# nanino.net
KiCad netlist of a schematic drawn in EAGLE
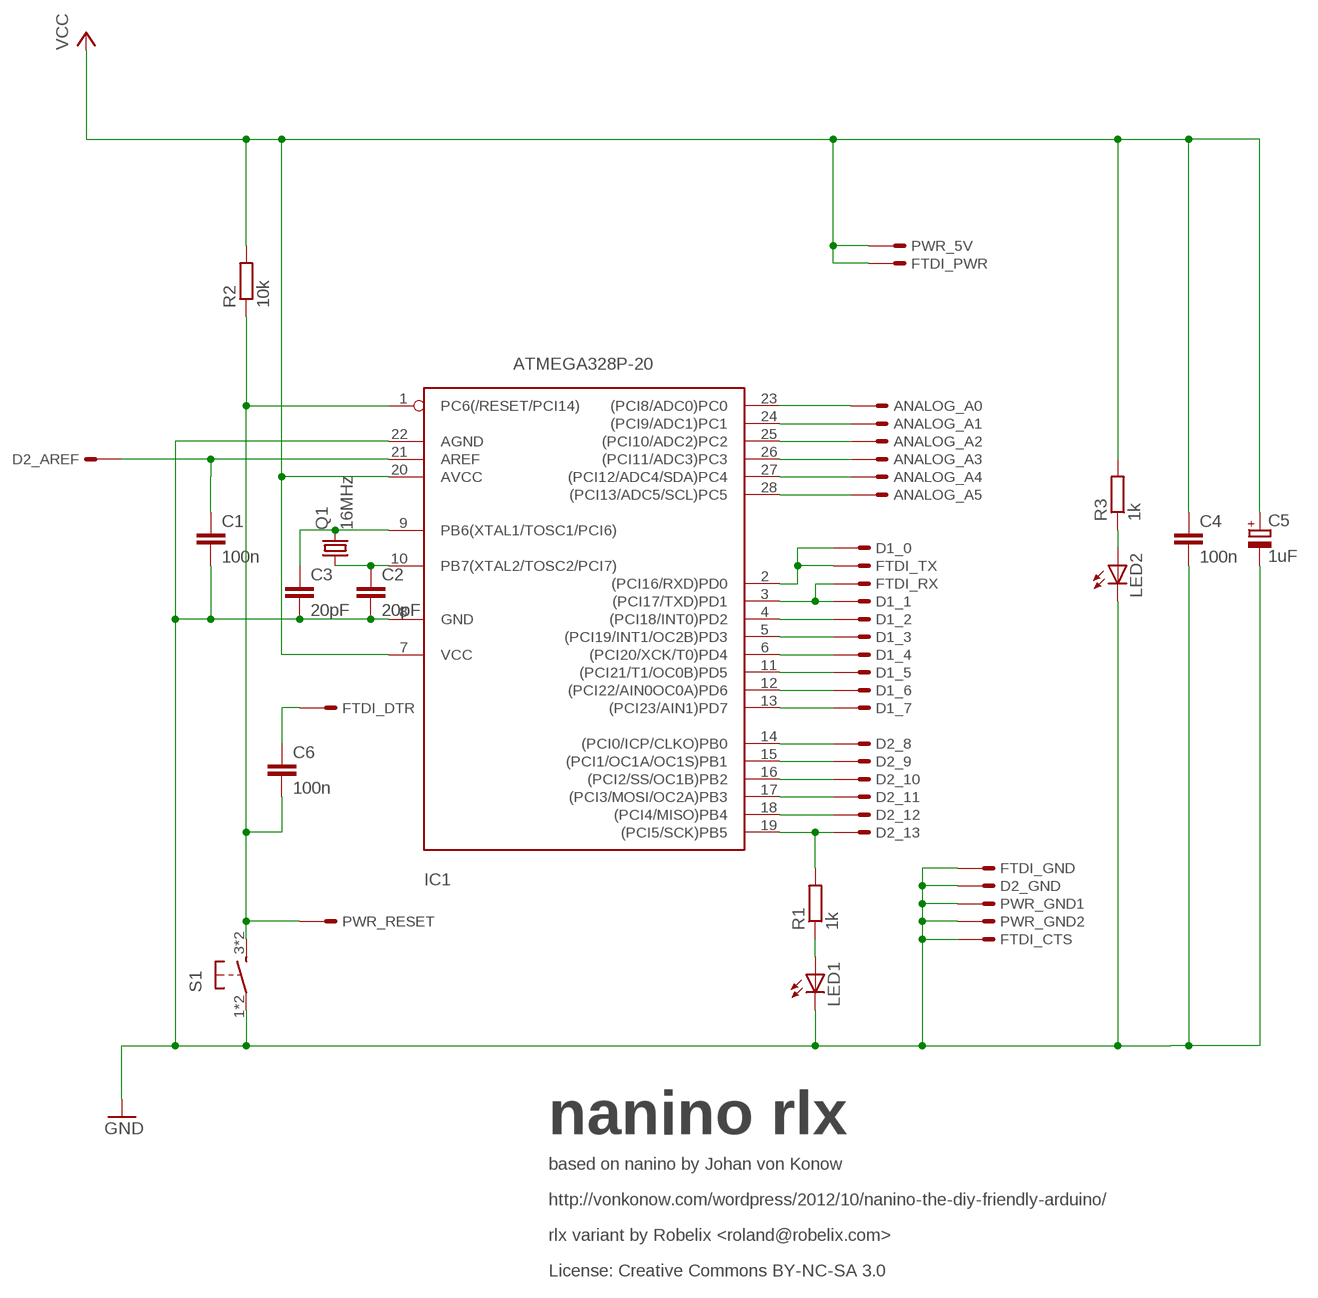
[diagram p0: schematic, sheet 1]

(export (version "E")
  (design (tool "Eeschema 10.0.6"))
  (components
    (comp (ref "ANALOG_")
      (value "PINS_ARDUINO_ANALOG1")
      (footprint "eagle-import:6PIN")
      (libsource (lib "eagle-import") (part "PINS_ARDUINO_ANALOG1"))
    )
    (comp (ref "C1")
      (value "100n")
      (footprint "eagle-import:C025-025X050")
      (libsource (lib "eagle-import") (part "C-EU025-025X050"))
    )
    (comp (ref "C2")
      (value "20pF")
      (footprint "eagle-import:C025-025X050")
      (libsource (lib "eagle-import") (part "C-EU025-025X050"))
    )
    (comp (ref "C3")
      (value "20pF")
      (footprint "eagle-import:C025-025X050")
      (libsource (lib "eagle-import") (part "C-EU025-025X050"))
    )
    (comp (ref "C4")
      (value "100n")
      (footprint "eagle-import:C025-025X050")
      (libsource (lib "eagle-import") (part "C-EU025-025X050"))
    )
    (comp (ref "C5")
      (value "1uF")
      (footprint "eagle-import:E2,5-5-L-12")
      (libsource (lib "eagle-import") (part "CPOL-EUE2.5-5-L-12"))
    )
    (comp (ref "C6")
      (value "100n")
      (footprint "eagle-import:C050-025X075")
      (libsource (lib "eagle-import") (part "C-EU050-025X075"))
    )
    (comp (ref "D1_")
      (value "PINS_ARDUINO_DIGITAL1")
      (footprint "eagle-import:8PIN")
      (libsource (lib "eagle-import") (part "PINS_ARDUINO_DIGITAL1"))
    )
    (comp (ref "D2_")
      (value "PINS_ARDUINO_DIGITAL2")
      (footprint "eagle-import:8PIN")
      (libsource (lib "eagle-import") (part "PINS_ARDUINO_DIGITAL2"))
    )
    (comp (ref "FTDI_")
      (value "PINS_FTDI1")
      (footprint "eagle-import:6PIN")
      (libsource (lib "eagle-import") (part "PINS_FTDI1"))
    )
    (comp (ref "IC1")
      (value "ATMEGA328P-20")
      (footprint "eagle-import:DIL28-3")
      (libsource (lib "eagle-import") (part "ATMEGA328P-20"))
    )
    (comp (ref "LED1")
      (value "LED3MM")
      (footprint "eagle-import:LED3MM")
      (libsource (lib "eagle-import") (part "LED3MM"))
    )
    (comp (ref "LED2")
      (value "LED3MM")
      (footprint "eagle-import:LED3MM")
      (libsource (lib "eagle-import") (part "LED3MM"))
    )
    (comp (ref "PWR_")
      (value "PINS_ARDUINO_PWR1")
      (footprint "eagle-import:6PIN")
      (libsource (lib "eagle-import") (part "PINS_ARDUINO_PWR1"))
    )
    (comp (ref "Q1")
      (value "16MHz")
      (footprint "eagle-import:HC49U-V")
      (libsource (lib "eagle-import") (part "CRYSTALHC49U-V"))
    )
    (comp (ref "R1")
      (value "1k")
      (footprint "eagle-import:0207_10")
      (libsource (lib "eagle-import") (part "R-EU_0207/10"))
    )
    (comp (ref "R2")
      (value "10k")
      (footprint "eagle-import:0207_10")
      (libsource (lib "eagle-import") (part "R-EU_0207/10"))
    )
    (comp (ref "R3")
      (value "1k")
      (footprint "eagle-import:0207_10")
      (libsource (lib "eagle-import") (part "R-EU_0207/10"))
    )
    (comp (ref "S1")
      (value "TASTER4.3MM")
      (footprint "eagle-import:TASTER6X6")
      (libsource (lib "eagle-import") (part "TASTER4.3MM"))
    )
  )
  (nets
    (net (code "1") (name "GND") (class "Default")
      (node (ref "C1") (pin "2") (pinfunction "2_2") (pintype "passive"))
      (node (ref "C2") (pin "2") (pinfunction "2_2") (pintype "passive"))
      (node (ref "C3") (pin "2") (pinfunction "2_2") (pintype "passive"))
      (node (ref "C4") (pin "2") (pinfunction "2_2") (pintype "passive"))
      (node (ref "C5") (pin "-") (pinfunction "-_-") (pintype "passive"))
      (node (ref "D2_") (pin "7") (pinfunction "S_7") (pintype "passive"))
      (node (ref "FTDI_") (pin "1") (pinfunction "S_1") (pintype "passive"))
      (node (ref "FTDI_") (pin "2") (pinfunction "S_2") (pintype "passive"))
      (node (ref "IC1") (pin "22") (pinfunction "AGND_22") (pintype "bidirectional"))
      (node (ref "IC1") (pin "8") (pinfunction "GND_8") (pintype "bidirectional"))
      (node (ref "LED1") (pin "K") (pinfunction "C_K") (pintype "passive"))
      (node (ref "LED2") (pin "K") (pinfunction "C_K") (pintype "passive"))
      (node (ref "PWR_") (pin "4") (pinfunction "S_4") (pintype "passive"))
      (node (ref "PWR_") (pin "5") (pinfunction "S_5") (pintype "passive"))
      (node (ref "S1") (pin "1") (pinfunction "1_1") (pintype "passive"))
      (node (ref "S1") (pin "2") (pinfunction "1_2") (pintype "passive"))
    )
    (net (code "2") (name "Net-(ANALOG_A-S)") (class "Default")
      (node (ref "ANALOG_") (pin "6") (pinfunction "S_6") (pintype "passive"))
      (node (ref "IC1") (pin "23") (pinfunction "(PCI8/ADC0)PC0_23") (pintype "bidirectional"))
    )
    (net (code "3") (name "Net-(ANALOG_B-S)") (class "Default")
      (node (ref "ANALOG_") (pin "5") (pinfunction "S_5") (pintype "passive"))
      (node (ref "IC1") (pin "24") (pinfunction "(PCI9/ADC1)PC1_24") (pintype "bidirectional"))
    )
    (net (code "4") (name "Net-(ANALOG_C-S)") (class "Default")
      (node (ref "ANALOG_") (pin "4") (pinfunction "S_4") (pintype "passive"))
      (node (ref "IC1") (pin "25") (pinfunction "(PCI10/ADC2)PC2_25") (pintype "bidirectional"))
    )
    (net (code "5") (name "Net-(ANALOG_D-S)") (class "Default")
      (node (ref "ANALOG_") (pin "3") (pinfunction "S_3") (pintype "passive"))
      (node (ref "IC1") (pin "26") (pinfunction "(PCI11/ADC3)PC3_26") (pintype "bidirectional"))
    )
    (net (code "6") (name "Net-(ANALOG_E-S)") (class "Default")
      (node (ref "ANALOG_") (pin "2") (pinfunction "S_2") (pintype "passive"))
      (node (ref "IC1") (pin "27") (pinfunction "(PCI12/ADC4/SDA)PC4_27") (pintype "bidirectional"))
    )
    (net (code "7") (name "Net-(ANALOG_F-S)") (class "Default")
      (node (ref "ANALOG_") (pin "1") (pinfunction "S_1") (pintype "passive"))
      (node (ref "IC1") (pin "28") (pinfunction "(PCI13/ADC5/SCL)PC5_28") (pintype "bidirectional"))
    )
    (net (code "8") (name "Net-(D1_A-S)") (class "Default")
      (node (ref "D1_") (pin "1") (pinfunction "S_1") (pintype "passive"))
      (node (ref "FTDI_") (pin "4") (pinfunction "S_4") (pintype "passive"))
      (node (ref "IC1") (pin "2") (pinfunction "(PCI16/RXD)PD0_2") (pintype "bidirectional"))
    )
    (net (code "9") (name "Net-(D1_B-S)") (class "Default")
      (node (ref "D1_") (pin "2") (pinfunction "S_2") (pintype "passive"))
      (node (ref "FTDI_") (pin "5") (pinfunction "S_5") (pintype "passive"))
      (node (ref "IC1") (pin "3") (pinfunction "(PCI17/TXD)PD1_3") (pintype "bidirectional"))
    )
    (net (code "10") (name "Net-(D1_C-S)") (class "Default")
      (node (ref "D1_") (pin "3") (pinfunction "S_3") (pintype "passive"))
      (node (ref "IC1") (pin "4") (pinfunction "(PCI18/INT0)PD2_4") (pintype "bidirectional"))
    )
    (net (code "11") (name "Net-(D1_D-S)") (class "Default")
      (node (ref "D1_") (pin "4") (pinfunction "S_4") (pintype "passive"))
      (node (ref "IC1") (pin "5") (pinfunction "(PCI19/INT1/OC2B)PD3_5") (pintype "bidirectional"))
    )
    (net (code "12") (name "Net-(D1_E-S)") (class "Default")
      (node (ref "D1_") (pin "5") (pinfunction "S_5") (pintype "passive"))
      (node (ref "IC1") (pin "6") (pinfunction "(PCI20/XCK/T0)PD4_6") (pintype "bidirectional"))
    )
    (net (code "13") (name "Net-(D1_F-S)") (class "Default")
      (node (ref "D1_") (pin "6") (pinfunction "S_6") (pintype "passive"))
      (node (ref "IC1") (pin "11") (pinfunction "(PCI21/T1/OC0B)PD5_11") (pintype "bidirectional"))
    )
    (net (code "14") (name "Net-(D1_G-S)") (class "Default")
      (node (ref "D1_") (pin "7") (pinfunction "S_7") (pintype "passive"))
      (node (ref "IC1") (pin "12") (pinfunction "(PCI22/AIN0OC0A)PD6_12") (pintype "bidirectional"))
    )
    (net (code "15") (name "Net-(D1_H-S)") (class "Default")
      (node (ref "D1_") (pin "8") (pinfunction "S_8") (pintype "passive"))
      (node (ref "IC1") (pin "13") (pinfunction "(PCI23/AIN1)PD7_13") (pintype "bidirectional"))
    )
    (net (code "16") (name "Net-(D2_A-S)") (class "Default")
      (node (ref "D2_") (pin "3") (pinfunction "S_3") (pintype "passive"))
      (node (ref "IC1") (pin "16") (pinfunction "(PCI2/SS/OC1B)PB2_16") (pintype "bidirectional"))
    )
    (net (code "17") (name "Net-(D2_B-S)") (class "Default")
      (node (ref "D2_") (pin "4") (pinfunction "S_4") (pintype "passive"))
      (node (ref "IC1") (pin "17") (pinfunction "(PCI3/MOSI/OC2A)PB3_17") (pintype "bidirectional"))
    )
    (net (code "18") (name "Net-(D2_C-S)") (class "Default")
      (node (ref "D2_") (pin "5") (pinfunction "S_5") (pintype "passive"))
      (node (ref "IC1") (pin "18") (pinfunction "(PCI4/MISO)PB4_18") (pintype "bidirectional"))
    )
    (net (code "19") (name "Net-(D2_D-S)") (class "Default")
      (node (ref "D2_") (pin "6") (pinfunction "S_6") (pintype "passive"))
      (node (ref "IC1") (pin "19") (pinfunction "(PCI5/SCK)PB5_19") (pintype "bidirectional"))
      (node (ref "R1") (pin "2") (pinfunction "2_2") (pintype "passive"))
    )
    (net (code "20") (name "Net-(D2_E-S)") (class "Default")
      (node (ref "D2_") (pin "1") (pinfunction "S_1") (pintype "passive"))
      (node (ref "IC1") (pin "14") (pinfunction "(PCI0/ICP/CLKO)PB0_14") (pintype "bidirectional"))
    )
    (net (code "21") (name "Net-(D2_F-S)") (class "Default")
      (node (ref "D2_") (pin "2") (pinfunction "S_2") (pintype "passive"))
      (node (ref "IC1") (pin "15") (pinfunction "(PCI1/OC1A/OC1S)PB1_15") (pintype "bidirectional"))
    )
    (net (code "22") (name "Net-(D2_G-S)") (class "Default")
      (node (ref "C1") (pin "1") (pinfunction "1_1") (pintype "passive"))
      (node (ref "D2_") (pin "8") (pinfunction "S_8") (pintype "passive"))
      (node (ref "IC1") (pin "21") (pinfunction "AREF_21") (pintype "bidirectional"))
    )
    (net (code "23") (name "Net-(FTDI_B-S)") (class "Default")
      (node (ref "C6") (pin "1") (pinfunction "1_1") (pintype "passive"))
      (node (ref "FTDI_") (pin "6") (pinfunction "S_6") (pintype "passive"))
    )
    (net (code "24") (name "Net-(IC1-PB6(XTAL1{slash}TOSC1{slash}PCI6))") (class "Default")
      (node (ref "C3") (pin "1") (pinfunction "1_1") (pintype "passive"))
      (node (ref "IC1") (pin "9") (pinfunction "PB6(XTAL1/TOSC1/PCI6)_9") (pintype "bidirectional"))
      (node (ref "Q1") (pin "2") (pinfunction "2_2") (pintype "passive"))
    )
    (net (code "25") (name "Net-(IC1-PB7(XTAL2{slash}TOSC2{slash}PCI7))") (class "Default")
      (node (ref "C2") (pin "1") (pinfunction "1_1") (pintype "passive"))
      (node (ref "IC1") (pin "10") (pinfunction "PB7(XTAL2/TOSC2/PCI7)_10") (pintype "bidirectional"))
      (node (ref "Q1") (pin "1") (pinfunction "1_1") (pintype "passive"))
    )
    (net (code "26") (name "Net-(IC1-PC6({slash}RESET{slash}PCI14))") (class "Default")
      (node (ref "C6") (pin "2") (pinfunction "2_2") (pintype "passive"))
      (node (ref "IC1") (pin "1") (pinfunction "PC6(/RESET/PCI14)_1") (pintype "bidirectional"))
      (node (ref "PWR_") (pin "1") (pinfunction "S_1") (pintype "passive"))
      (node (ref "R2") (pin "1") (pinfunction "1_1") (pintype "passive"))
      (node (ref "S1") (pin "3") (pinfunction "3_3") (pintype "passive"))
      (node (ref "S1") (pin "4") (pinfunction "3_4") (pintype "passive"))
    )
    (net (code "27") (name "Net-(LED1-PadA)") (class "Default")
      (node (ref "LED1") (pin "A") (pinfunction "A_A") (pintype "passive"))
      (node (ref "R1") (pin "1") (pinfunction "1_1") (pintype "passive"))
    )
    (net (code "28") (name "Net-(LED2-PadA)") (class "Default")
      (node (ref "LED2") (pin "A") (pinfunction "A_A") (pintype "passive"))
      (node (ref "R3") (pin "1") (pinfunction "1_1") (pintype "passive"))
    )
    (net (code "29") (name "VCC") (class "Default")
      (node (ref "C4") (pin "1") (pinfunction "1_1") (pintype "passive"))
      (node (ref "C5") (pin "+") (pinfunction "+_+") (pintype "passive"))
      (node (ref "FTDI_") (pin "3") (pinfunction "S_3") (pintype "passive"))
      (node (ref "IC1") (pin "20") (pinfunction "AVCC_20") (pintype "bidirectional"))
      (node (ref "IC1") (pin "7") (pinfunction "VCC_7") (pintype "bidirectional"))
      (node (ref "PWR_") (pin "3") (pinfunction "S_3") (pintype "passive"))
      (node (ref "R2") (pin "2") (pinfunction "2_2") (pintype "passive"))
      (node (ref "R3") (pin "2") (pinfunction "2_2") (pintype "passive"))
    )
  )
)
